# holiday_detector.net
KiCad netlist of a schematic drawn in Altium Designer
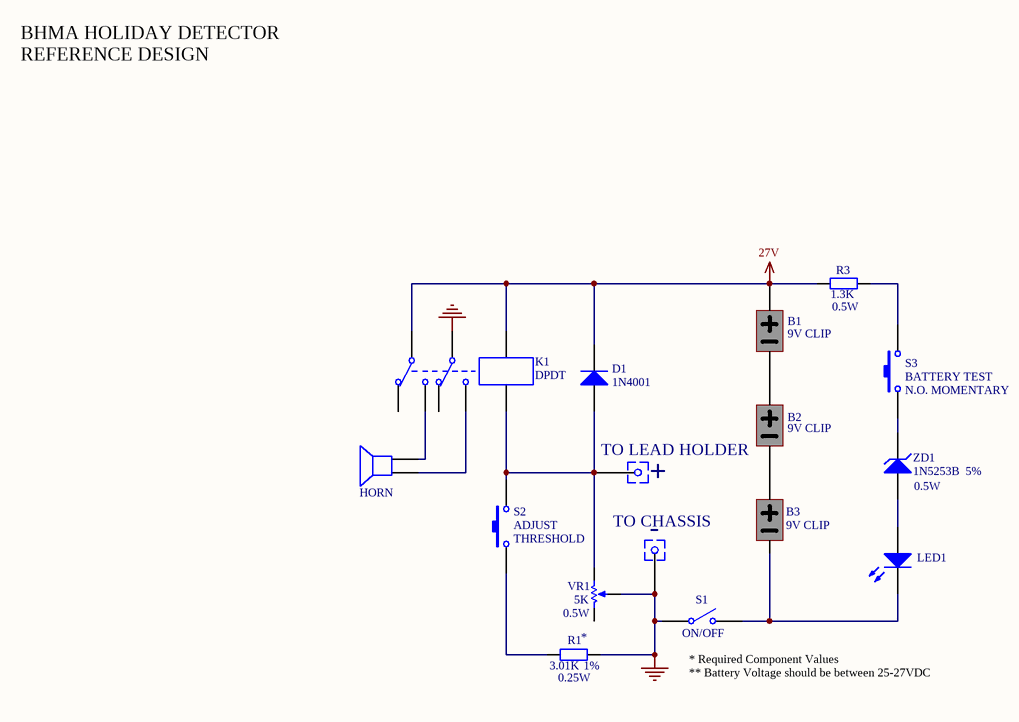
[diagram p0: holiday_detector.SchDoc]

(export (version "E")
  (design (tool "Eeschema 10.0.6"))
  (components
    (comp (ref "+") (value "TP_80_MIL") (footprint "TP_80_MIL") (libsource (lib "Train2") (part "TP_80_MIL")))
    (comp (ref "- CHASSIS")
      (value "TP_80_MIL")
      (footprint "TP_80_MIL")
      (libsource (lib "Train2") (part "TP_80_MIL"))
    )
    (comp (ref "B1")
      (value "9V CLIP")
      (footprint "BATT_CLIP")
      (description "PCB MOUNT 9V BATTERY CLIP")
      (fields (field (name "MFR") "KEYSTONE"))
      (libsource (lib "") (part "BATT_CLIP_1"))
    )
    (comp (ref "B2")
      (value "9V CLIP")
      (footprint "BATT_CLIP")
      (description "PCB MOUNT 9V BATTERY CLIP")
      (fields (field (name "MFR") "KEYSTONE"))
      (libsource (lib "") (part "BATT_CLIP_1"))
    )
    (comp (ref "B3")
      (value "9V CLIP")
      (footprint "BATT_CLIP")
      (description "PCB MOUNT 9V BATTERY CLIP")
      (fields (field (name "MFR") "KEYSTONE"))
      (libsource (lib "Train2") (part "BATT_CLIP"))
    )
    (comp (ref "D1")
      (value "1N4001")
      (footprint "DO-41")
      (description "1 Amp General Purpose Rectifier")
      (libsource (lib "Miscellaneous Devices") (part "Diode 1N4001"))
    )
    (comp (ref "HORN")
      (value "Speaker")
      (footprint "BUZZER")
      (description "Loudspeaker")
      (fields (field (name "PUBLISHER") "Altium Limited"))
      (libsource (lib "Miscellaneous Devices") (part "Speaker"))
    )
    (comp (ref "K1")
      (value "DPDT")
      (footprint "OM_G2R")
      (description "Dual-Pole Dual-Throw Relay")
      (libsource (lib "Miscellaneous Devices") (part "Relay-DPDT"))
    )
    (comp (ref "LED1")
      (value "T-1 3/4")
      (footprint "LED_2")
      (description "Typical RED GaAs LED")
      (fields (field (name "PUBLISHER") "Altium Limited"))
      (libsource (lib "Miscellaneous Devices") (part "LED1"))
    )
    (comp (ref "R1")
      (value "3.01K")
      (footprint "AXIAL-0.4")
      (description "Resistor")
      (fields
        (field (name "TOLERANCE") "1%")
        (field (name "POWER RATING") "0.25W")
        (field (name "MFR PART") "SFR55")
        (field (name "MFR") "PHILLIPS")
      )
      (libsource (lib "Miscellaneous Devices") (part "Res2"))
    )
    (comp (ref "R3")
      (value "1.3K")
      (footprint "AXIAL-0.4")
      (description "Resistor")
      (fields
        (field (name "TOLERANCE") "5%")
        (field (name "POWER RATING") "0.5W")
        (field (name "Comment") "Res2")
      )
      (libsource (lib "") (part "Res2_1"))
    )
    (comp (ref "S1")
      (value "ON/OFF")
      (footprint "SPDT_PCB - duplicate")
      (description "SPST SLIDE SW")
      (libsource (lib "Miscellaneous Devices") (part "SW-SPST"))
    )
    (comp (ref "S2")
      (value "ADJUST")
      (footprint "SPST-2")
      (description "TACTILE SW")
      (fields (field (name "PUBLISHER") "Altium Limited"))
      (libsource (lib "Miscellaneous Devices") (part "SW-PB"))
    )
    (comp (ref "S3")
      (value "BATTERY TEST")
      (footprint "SPST-2")
      (description "TACTILE SW")
      (fields (field (name "TYPE") "N.O. MOMENTARY") (field (name "PUBLISHER") "Altium Limited"))
      (libsource (lib "Miscellaneous Devices") (part "SW-PB"))
    )
    (comp (ref "VR1")
      (value "5K")
      (footprint "JMP3")
      (description "Potentiometer")
      (fields
        (field (name "POWER RATING") "0.5W")
        (field (name "MFR PART") "308N")
        (field (name "MFR") "Clarostat")
      )
      (libsource (lib "Miscellaneous Devices") (part "RPot"))
    )
    (comp (ref "ZD1")
      (value "*")
      (footprint "ZENER_1_WATT")
      (description "Zener Diode")
      (fields
        (field (name "VOLTAGE") "1N5253B")
        (field (name "TOLERANCE") "5%")
        (field (name "POWER RATING") "0.5W")
      )
      (libsource (lib "Miscellaneous Devices") (part "D Zener"))
    )
  )
  (nets
    (net (code "1") (name "27V") (class "Default")
      (node (ref "B1") (pin "1") (pinfunction "POS_1") (pintype "passive"))
      (node (ref "D1") (pin "2") (pinfunction "K_2") (pintype "passive"))
      (node (ref "K1") (pin "3") (pinfunction "3_3") (pintype "passive"))
      (node (ref "K1") (pin "8") (pinfunction "8_8") (pintype "passive"))
      (node (ref "R3") (pin "2") (pinfunction "2_2") (pintype "passive"))
    )
    (net (code "2") (name "GND") (class "Default")
      (node (ref "- CHASSIS") (pin "1") (pinfunction "1_1") (pintype "passive"))
      (node (ref "K1") (pin "6") (pinfunction "6_6") (pintype "passive"))
      (node (ref "R1") (pin "2") (pinfunction "2_2") (pintype "passive"))
      (node (ref "S1") (pin "1") (pinfunction "COMMON_1") (pintype "passive"))
      (node (ref "VR1") (pin "3") (pinfunction "TAP_3") (pintype "passive"))
    )
    (net (code "3") (name "Net-(B1-NEG)") (class "Default")
      (node (ref "B1") (pin "2") (pinfunction "NEG_2") (pintype "power_in"))
      (node (ref "B2") (pin "1") (pinfunction "POS_1") (pintype "passive"))
    )
    (net (code "4") (name "Net-(B2-NEG)") (class "Default")
      (node (ref "B2") (pin "2") (pinfunction "NEG_2") (pintype "power_in"))
      (node (ref "B3") (pin "1") (pinfunction "POS_1") (pintype "passive"))
    )
    (net (code "5") (name "Net-(B3-NEG)") (class "Default")
      (node (ref "B3") (pin "2") (pinfunction "NEG_2") (pintype "power_in"))
      (node (ref "LED1") (pin "2") (pinfunction "K_2") (pintype "passive"))
      (node (ref "S1") (pin "2") (pinfunction "NO_2") (pintype "passive"))
    )
    (net (code "6") (name "Net-(D1-A)") (class "Default")
      (node (ref "+") (pin "1") (pinfunction "1_1") (pintype "passive"))
      (node (ref "D1") (pin "1") (pinfunction "A_1") (pintype "passive"))
      (node (ref "K1") (pin "1") (pinfunction "1_1") (pintype "passive"))
      (node (ref "S2") (pin "1") (pinfunction "1_1") (pintype "passive"))
      (node (ref "VR1") (pin "1") (pinfunction "TOP_1") (pintype "passive"))
    )
    (net (code "7") (name "Net-(HORN-Pad1)") (class "Default")
      (node (ref "HORN") (pin "1") (pinfunction "1_1") (pintype "passive"))
      (node (ref "K1") (pin "4") (pinfunction "4_4") (pintype "passive"))
    )
    (net (code "8") (name "Net-(HORN-Pad2)") (class "Default")
      (node (ref "HORN") (pin "2") (pinfunction "2_2") (pintype "passive"))
      (node (ref "K1") (pin "5") (pinfunction "5_5") (pintype "passive"))
    )
    (net (code "9") (name "Net-(LED1-A)") (class "Default")
      (node (ref "LED1") (pin "1") (pinfunction "A_1") (pintype "passive"))
      (node (ref "ZD1") (pin "1") (pinfunction "A_1") (pintype "passive"))
    )
    (net (code "10") (name "Net-(R1-Pad1)") (class "Default")
      (node (ref "R1") (pin "1") (pinfunction "1_1") (pintype "passive"))
      (node (ref "S2") (pin "2") (pinfunction "2_2") (pintype "passive"))
    )
    (net (code "11") (name "Net-(R3-Pad1)") (class "Default")
      (node (ref "R3") (pin "1") (pinfunction "1_1") (pintype "passive"))
      (node (ref "S3") (pin "1") (pinfunction "1_1") (pintype "passive"))
    )
    (net (code "12") (name "Net-(ZD1-K)") (class "Default")
      (node (ref "S3") (pin "2") (pinfunction "2_2") (pintype "passive"))
      (node (ref "ZD1") (pin "2") (pinfunction "K_2") (pintype "passive"))
    )
    (net (code "13") (name "unconnected-(K1-Pad2)") (class "Default")
      (node (ref "K1") (pin "2") (pinfunction "2_2") (pintype "passive"))
    )
    (net (code "14") (name "unconnected-(K1-Pad7)") (class "Default")
      (node (ref "K1") (pin "7") (pinfunction "7_7") (pintype "passive"))
    )
    (net (code "15") (name "unconnected-(VR1-BOT-Pad2)") (class "Default")
      (node (ref "VR1") (pin "2") (pinfunction "BOT_2") (pintype "passive"))
    )
  )
)
